# gordian-knot.net
KiCad netlist of a schematic drawn in EAGLE
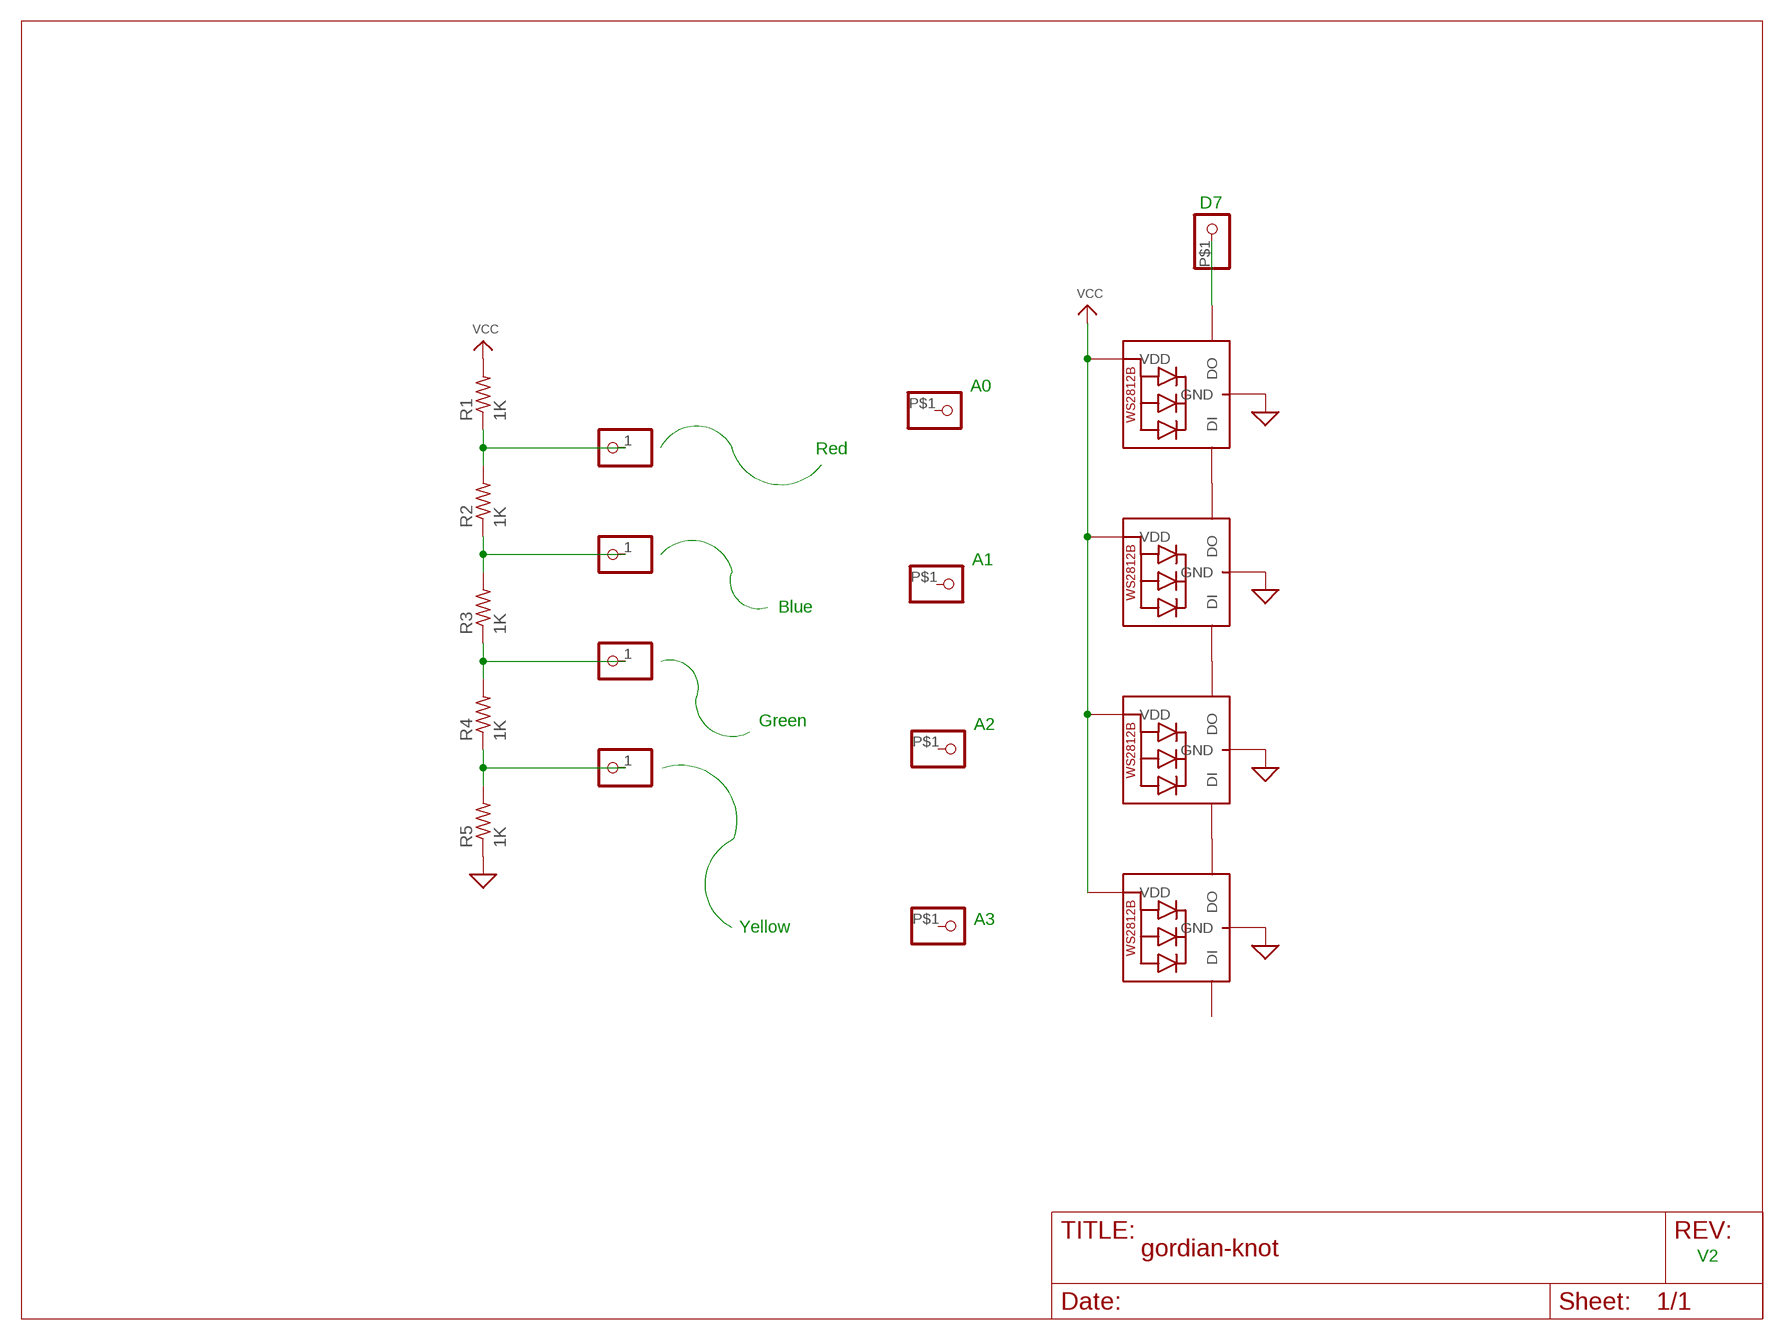
[diagram p0: schematic, sheet 1]

(export (version "E")
  (design (tool "Eeschema 10.0.6"))
  (components
    (comp (ref "JP1")
      (value "PINHD-1X1-BIGPOGO")
      (footprint "eagle-import:1X1-BIGPOGO")
      (libsource (lib "eagle-import") (part "PINHD-1X1-BIGPOGO"))
    )
    (comp (ref "JP2")
      (value "PINHD-1X1")
      (footprint "eagle-import:1X01")
      (libsource (lib "eagle-import") (part "PINHD-1X1"))
    )
    (comp (ref "JP3")
      (value "PINHD-1X1-BIGPOGO")
      (footprint "eagle-import:1X1-BIGPOGO")
      (libsource (lib "eagle-import") (part "PINHD-1X1-BIGPOGO"))
    )
    (comp (ref "JP4")
      (value "PINHD-1X1")
      (footprint "eagle-import:1X01")
      (libsource (lib "eagle-import") (part "PINHD-1X1"))
    )
    (comp (ref "JP5")
      (value "PINHD-1X1-BIGPOGO")
      (footprint "eagle-import:1X1-BIGPOGO")
      (libsource (lib "eagle-import") (part "PINHD-1X1-BIGPOGO"))
    )
    (comp (ref "JP6")
      (value "PINHD-1X1")
      (footprint "eagle-import:1X01")
      (libsource (lib "eagle-import") (part "PINHD-1X1"))
    )
    (comp (ref "JP7")
      (value "PINHD-1X1-BIGPOGO")
      (footprint "eagle-import:1X1-BIGPOGO")
      (libsource (lib "eagle-import") (part "PINHD-1X1-BIGPOGO"))
    )
    (comp (ref "JP8")
      (value "PINHD-1X1")
      (footprint "eagle-import:1X01")
      (libsource (lib "eagle-import") (part "PINHD-1X1"))
    )
    (comp (ref "JP10")
      (value "PINHD-1X1-BIGPOGO")
      (footprint "eagle-import:1X1-BIGPOGO")
      (libsource (lib "eagle-import") (part "PINHD-1X1-BIGPOGO"))
    )
    (comp (ref "LED1")
      (value "WS2812B5050")
      (footprint "eagle-import:WS2812B")
      (libsource (lib "eagle-import") (part "WS2812B5050"))
    )
    (comp (ref "LED2")
      (value "WS2812B5050")
      (footprint "eagle-import:WS2812B")
      (libsource (lib "eagle-import") (part "WS2812B5050"))
    )
    (comp (ref "LED3")
      (value "WS2812B5050")
      (footprint "eagle-import:WS2812B")
      (libsource (lib "eagle-import") (part "WS2812B5050"))
    )
    (comp (ref "LED4")
      (value "WS2812B5050")
      (footprint "eagle-import:WS2812B")
      (libsource (lib "eagle-import") (part "WS2812B5050"))
    )
    (comp (ref "R1")
      (value "1K")
      (footprint "eagle-import:0207_9")
      (libsource (lib "eagle-import") (part "R-US_0207/9"))
    )
    (comp (ref "R2")
      (value "1K")
      (footprint "eagle-import:0207_9")
      (libsource (lib "eagle-import") (part "R-US_0207/9"))
    )
    (comp (ref "R3")
      (value "1K")
      (footprint "eagle-import:0207_9")
      (libsource (lib "eagle-import") (part "R-US_0207/9"))
    )
    (comp (ref "R4")
      (value "1K")
      (footprint "eagle-import:0207_9")
      (libsource (lib "eagle-import") (part "R-US_0207/9"))
    )
    (comp (ref "R5")
      (value "1K")
      (footprint "eagle-import:0207_9")
      (libsource (lib "eagle-import") (part "R-US_0207/9"))
    )
  )
  (nets
    (net (code "1") (name "Net-(JP2-Pad1)") (class "Default")
      (node (ref "JP2") (pin "1") (pinfunction "1_1") (pintype "passive"))
      (node (ref "R1") (pin "1") (pinfunction "1_1") (pintype "passive"))
      (node (ref "R2") (pin "2") (pinfunction "2_2") (pintype "passive"))
    )
    (net (code "2") (name "Net-(JP4-Pad1)") (class "Default")
      (node (ref "JP4") (pin "1") (pinfunction "1_1") (pintype "passive"))
      (node (ref "R2") (pin "1") (pinfunction "1_1") (pintype "passive"))
      (node (ref "R3") (pin "2") (pinfunction "2_2") (pintype "passive"))
    )
    (net (code "3") (name "Net-(JP6-Pad1)") (class "Default")
      (node (ref "JP6") (pin "1") (pinfunction "1_1") (pintype "passive"))
      (node (ref "R3") (pin "1") (pinfunction "1_1") (pintype "passive"))
      (node (ref "R4") (pin "2") (pinfunction "2_2") (pintype "passive"))
    )
    (net (code "4") (name "Net-(JP8-Pad1)") (class "Default")
      (node (ref "JP8") (pin "1") (pinfunction "1_1") (pintype "passive"))
      (node (ref "R4") (pin "1") (pinfunction "1_1") (pintype "passive"))
      (node (ref "R5") (pin "2") (pinfunction "2_2") (pintype "passive"))
    )
    (net (code "5") (name "Net-(JP10-1)") (class "Default")
      (node (ref "JP10") (pin "P$1") (pinfunction "1_P$1") (pintype "passive"))
      (node (ref "LED1") (pin "2-DOUT") (pinfunction "DO_2-DOUT") (pintype "output"))
    )
    (net (code "6") (name "Net-(LED1-DI)") (class "Default")
      (node (ref "LED1") (pin "4-DIN") (pinfunction "DI_4-DIN") (pintype "input"))
      (node (ref "LED2") (pin "2-DOUT") (pinfunction "DO_2-DOUT") (pintype "output"))
    )
    (net (code "7") (name "Net-(LED2-DI)") (class "Default")
      (node (ref "LED2") (pin "4-DIN") (pinfunction "DI_4-DIN") (pintype "input"))
      (node (ref "LED3") (pin "2-DOUT") (pinfunction "DO_2-DOUT") (pintype "output"))
    )
    (net (code "8") (name "Net-(LED3-DI)") (class "Default")
      (node (ref "LED3") (pin "4-DIN") (pinfunction "DI_4-DIN") (pintype "input"))
      (node (ref "LED4") (pin "2-DOUT") (pinfunction "DO_2-DOUT") (pintype "output"))
    )
    (net (code "9") (name "SUP") (class "Default")
      (node (ref "LED1") (pin "3-GND") (pinfunction "GND_3-GND") (pintype "power_in"))
      (node (ref "LED2") (pin "3-GND") (pinfunction "GND_3-GND") (pintype "power_in"))
      (node (ref "LED3") (pin "3-GND") (pinfunction "GND_3-GND") (pintype "power_in"))
      (node (ref "LED4") (pin "3-GND") (pinfunction "GND_3-GND") (pintype "power_in"))
      (node (ref "R5") (pin "1") (pinfunction "1_1") (pintype "passive"))
    )
    (net (code "10") (name "VCC") (class "Default")
      (node (ref "LED1") (pin "1-VDD") (pinfunction "VDD_1-VDD") (pintype "power_in"))
      (node (ref "LED2") (pin "1-VDD") (pinfunction "VDD_1-VDD") (pintype "power_in"))
      (node (ref "LED3") (pin "1-VDD") (pinfunction "VDD_1-VDD") (pintype "power_in"))
      (node (ref "LED4") (pin "1-VDD") (pinfunction "VDD_1-VDD") (pintype "power_in"))
      (node (ref "R1") (pin "2") (pinfunction "2_2") (pintype "passive"))
    )
    (net (code "11") (name "unconnected-(JP1-1-PadP$1)") (class "Default")
      (node (ref "JP1") (pin "P$1") (pinfunction "1_P$1") (pintype "passive"))
    )
    (net (code "12") (name "unconnected-(JP3-1-PadP$1)") (class "Default")
      (node (ref "JP3") (pin "P$1") (pinfunction "1_P$1") (pintype "passive"))
    )
    (net (code "13") (name "unconnected-(JP5-1-PadP$1)") (class "Default")
      (node (ref "JP5") (pin "P$1") (pinfunction "1_P$1") (pintype "passive"))
    )
    (net (code "14") (name "unconnected-(JP7-1-PadP$1)") (class "Default")
      (node (ref "JP7") (pin "P$1") (pinfunction "1_P$1") (pintype "passive"))
    )
    (net (code "15") (name "unconnected-(LED4-DI-Pad4-DIN)") (class "Default")
      (node (ref "LED4") (pin "4-DIN") (pinfunction "DI_4-DIN") (pintype "input"))
    )
  )
)
